# Helicopter_Control_Board2.net
KiCad netlist of a schematic drawn in EAGLE
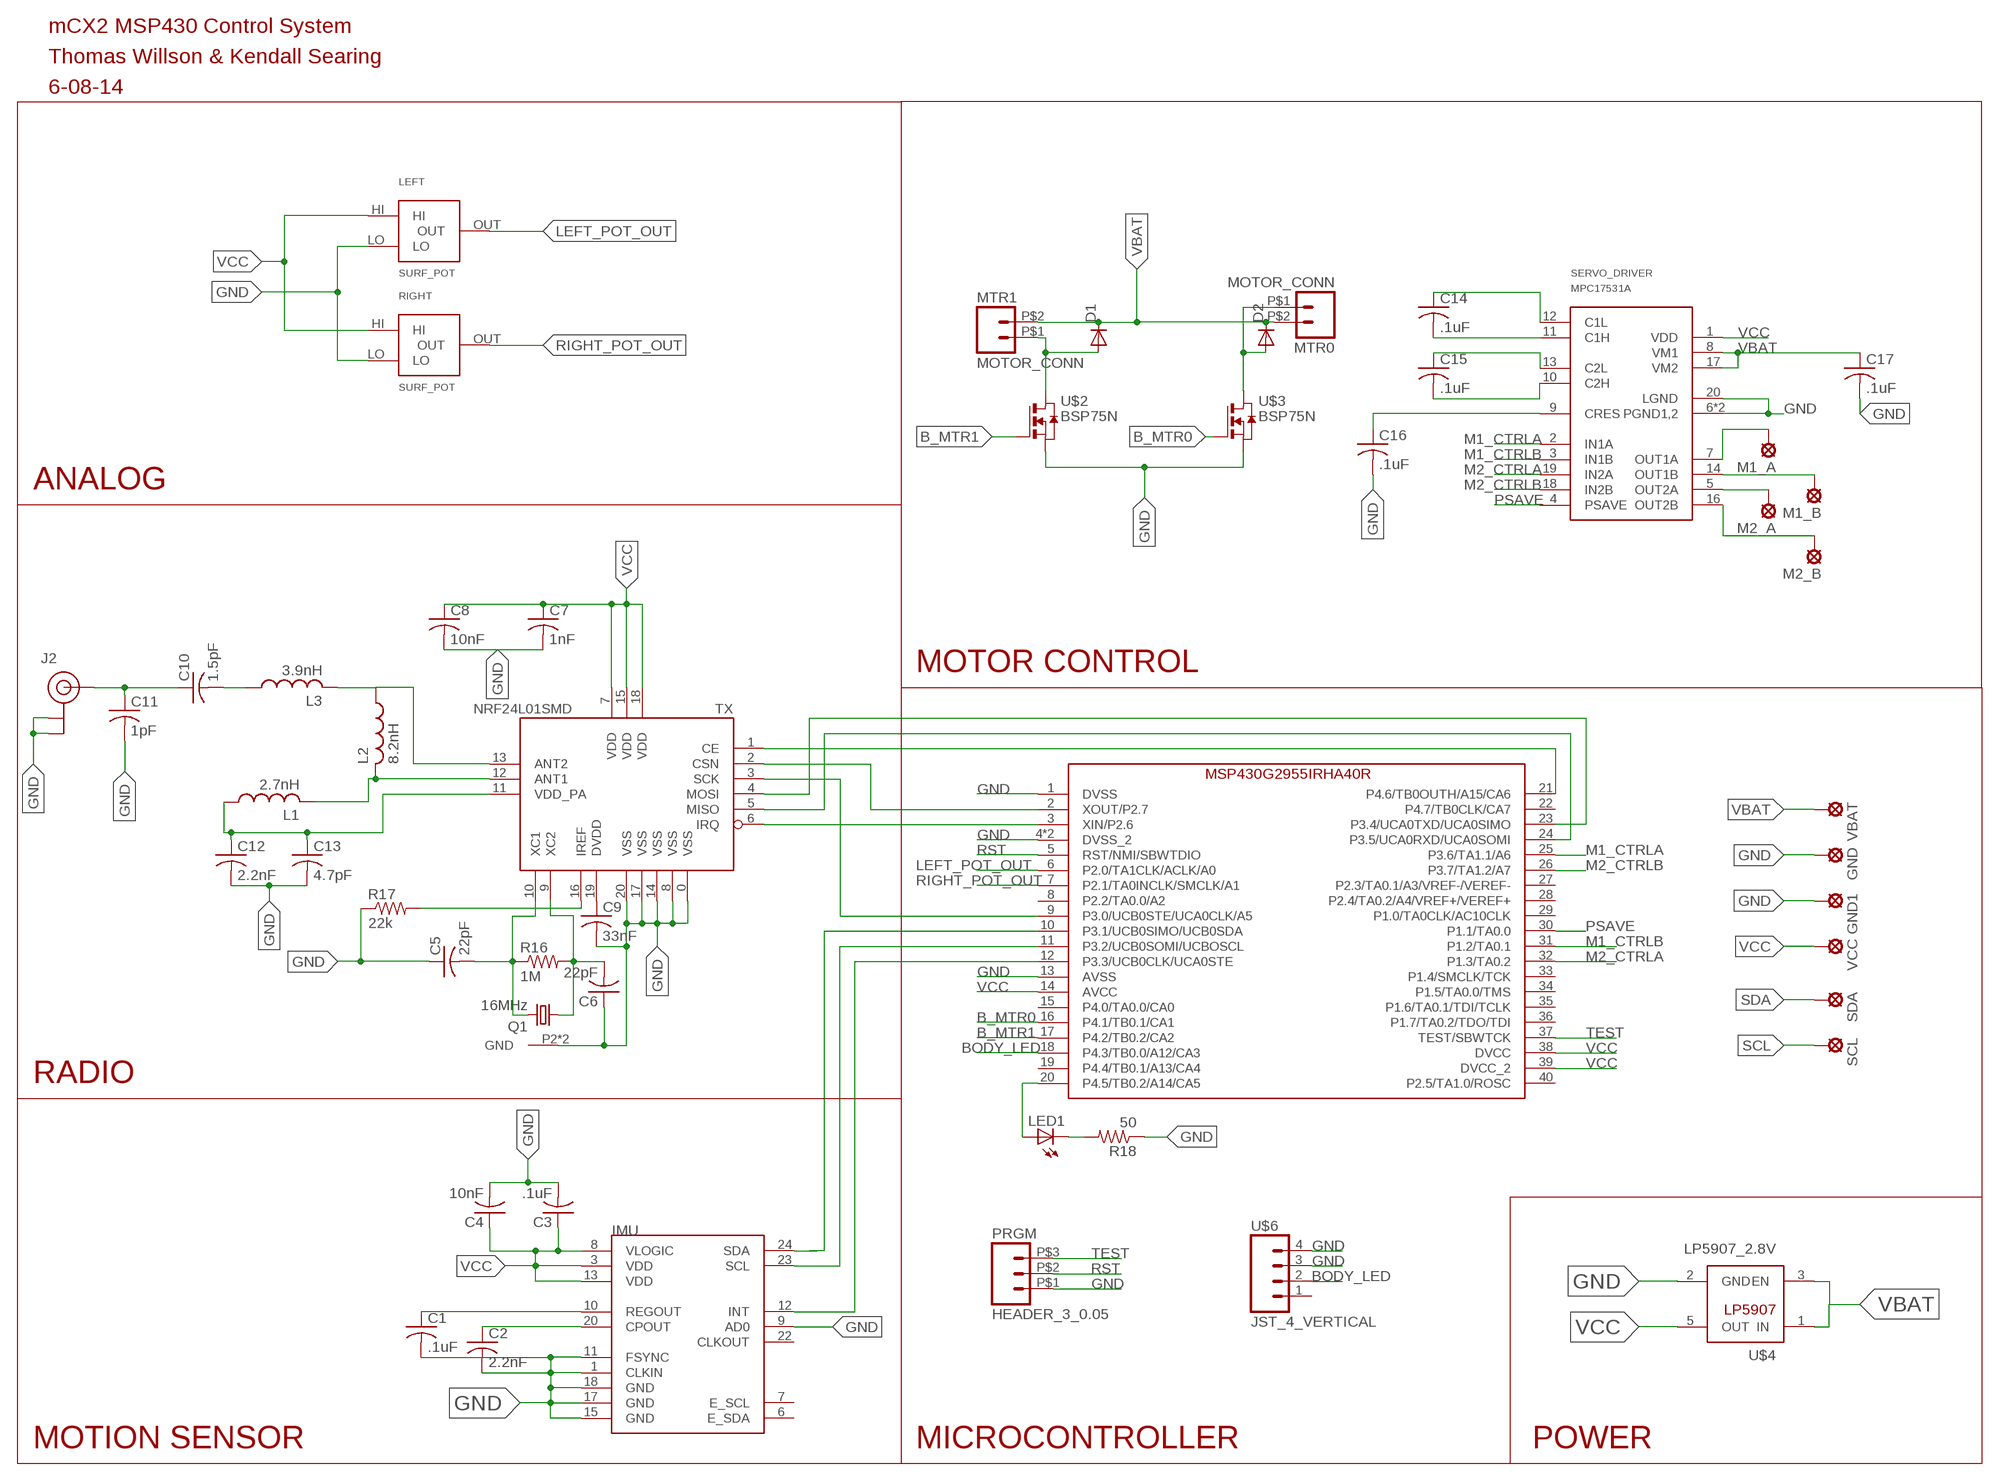
[diagram p0: schematic, sheet 1]

(export (version "E")
  (design (tool "Eeschema 10.0.6"))
  (components
    (comp (ref "C1")
      (value ".1uF")
      (footprint "eagle-import:C0402")
      (libsource (lib "eagle-import") (part "C-USC0402"))
    )
    (comp (ref "C2")
      (value "2.2nF")
      (footprint "eagle-import:C0402")
      (libsource (lib "eagle-import") (part "C-USC0402"))
    )
    (comp (ref "C3")
      (value ".1uF")
      (footprint "eagle-import:C0402")
      (libsource (lib "eagle-import") (part "C-USC0402"))
    )
    (comp (ref "C4")
      (value "10nF")
      (footprint "eagle-import:C0402")
      (libsource (lib "eagle-import") (part "C-USC0402"))
    )
    (comp (ref "C5")
      (value "22pF")
      (footprint "eagle-import:C0402")
      (libsource (lib "eagle-import") (part "C-USC0402"))
    )
    (comp (ref "C6")
      (value "22pF")
      (footprint "eagle-import:C0402")
      (libsource (lib "eagle-import") (part "C-USC0402"))
    )
    (comp (ref "C7")
      (value "1nF")
      (footprint "eagle-import:C0402")
      (libsource (lib "eagle-import") (part "C-USC0402"))
    )
    (comp (ref "C8")
      (value "10nF")
      (footprint "eagle-import:C0402")
      (libsource (lib "eagle-import") (part "C-USC0402"))
    )
    (comp (ref "C9")
      (value "33nF")
      (footprint "eagle-import:C0402")
      (libsource (lib "eagle-import") (part "C-USC0402"))
    )
    (comp (ref "C10")
      (value "1.5pF")
      (footprint "eagle-import:C0402")
      (libsource (lib "eagle-import") (part "C-USC0402"))
    )
    (comp (ref "C11")
      (value "1pF")
      (footprint "eagle-import:C0402")
      (libsource (lib "eagle-import") (part "C-USC0402"))
    )
    (comp (ref "C12")
      (value "2.2nF")
      (footprint "eagle-import:C0402")
      (libsource (lib "eagle-import") (part "C-USC0402"))
    )
    (comp (ref "C13")
      (value "4.7pF")
      (footprint "eagle-import:C0402")
      (libsource (lib "eagle-import") (part "C-USC0402"))
    )
    (comp (ref "C14")
      (value ".1uF")
      (footprint "eagle-import:C0402")
      (libsource (lib "eagle-import") (part "C-USC0402"))
    )
    (comp (ref "C15")
      (value ".1uF")
      (footprint "eagle-import:C0402")
      (libsource (lib "eagle-import") (part "C-USC0402"))
    )
    (comp (ref "C16")
      (value ".1uF")
      (footprint "eagle-import:C0402")
      (libsource (lib "eagle-import") (part "C-USC0402"))
    )
    (comp (ref "C17")
      (value ".1uF")
      (footprint "eagle-import:C0402")
      (libsource (lib "eagle-import") (part "C-USC0402"))
    )
    (comp (ref "D1")
      (value "DIODESMA")
      (footprint "eagle-import:SMA-DIODE")
      (libsource (lib "eagle-import") (part "DIODESMA"))
    )
    (comp (ref "D2")
      (value "DIODESMA")
      (footprint "eagle-import:SMA-DIODE")
      (libsource (lib "eagle-import") (part "DIODESMA"))
    )
    (comp (ref "GND")
      (value "LSP10")
      (footprint "eagle-import:LSP10")
      (libsource (lib "eagle-import") (part "LSP10"))
    )
    (comp (ref "GND1")
      (value "LSP10")
      (footprint "eagle-import:LSP10")
      (libsource (lib "eagle-import") (part "LSP10"))
    )
    (comp (ref "IMU")
      (value "MPU-9150QFN-24-NP")
      (footprint "eagle-import:QFN-24-NP")
      (libsource (lib "eagle-import") (part "MPU-9150QFN-24-NP"))
    )
    (comp (ref "J2")
      (value "U.FL")
      (footprint "eagle-import:U.FL")
      (libsource (lib "eagle-import") (part "U.FL"))
    )
    (comp (ref "L1")
      (value "2.7nH")
      (footprint "eagle-import:R0402")
      (libsource (lib "eagle-import") (part "L-US"))
    )
    (comp (ref "L2")
      (value "8.2nH")
      (footprint "eagle-import:R0402")
      (libsource (lib "eagle-import") (part "L-US"))
    )
    (comp (ref "L3")
      (value "3.9nH")
      (footprint "eagle-import:R0402")
      (libsource (lib "eagle-import") (part "L-US"))
    )
    (comp (ref "LED1")
      (value "LED-BLUE0603")
      (footprint "eagle-import:LED-0603")
      (libsource (lib "eagle-import") (part "LED-BLUE0603"))
    )
    (comp (ref "LEFT")
      (value "SURF_POT")
      (footprint "eagle-import:SURF_POT")
      (libsource (lib "eagle-import") (part "SURF_POT"))
    )
    (comp (ref "M1_A")
      (value "LSP10")
      (footprint "eagle-import:LSP10")
      (libsource (lib "eagle-import") (part "LSP10"))
    )
    (comp (ref "M1_B")
      (value "LSP10")
      (footprint "eagle-import:LSP10")
      (libsource (lib "eagle-import") (part "LSP10"))
    )
    (comp (ref "M2_A")
      (value "LSP10")
      (footprint "eagle-import:LSP10")
      (libsource (lib "eagle-import") (part "LSP10"))
    )
    (comp (ref "M2_B")
      (value "LSP10")
      (footprint "eagle-import:LSP10")
      (libsource (lib "eagle-import") (part "LSP10"))
    )
    (comp (ref "MTR0")
      (value "MOTOR_CONN")
      (footprint "eagle-import:MOTOR_CONN")
      (libsource (lib "eagle-import") (part "MOTOR_CONN"))
    )
    (comp (ref "MTR1")
      (value "MOTOR_CONN")
      (footprint "eagle-import:MOTOR_CONN")
      (libsource (lib "eagle-import") (part "MOTOR_CONN"))
    )
    (comp (ref "PRGM")
      (value "HEADER_3_0.05")
      (footprint "eagle-import:HEADER_3_.05")
      (libsource (lib "eagle-import") (part "HEADER_3_0.05"))
    )
    (comp (ref "Q1")
      (value "16MHz")
      (footprint "eagle-import:TXC-4SMD")
      (libsource (lib "eagle-import") (part "CRYSTAL_16MHZ_12PF_SMD"))
    )
    (comp (ref "R16")
      (value "1M")
      (footprint "eagle-import:R0402")
      (libsource (lib "eagle-import") (part "R-US_R0402"))
    )
    (comp (ref "R17")
      (value "22k")
      (footprint "eagle-import:R0402")
      (libsource (lib "eagle-import") (part "R-US_R0402"))
    )
    (comp (ref "R18")
      (value "50")
      (footprint "eagle-import:R0603")
      (libsource (lib "eagle-import") (part "R-US_R0603"))
    )
    (comp (ref "RIGHT")
      (value "SURF_POT")
      (footprint "eagle-import:SURF_POT")
      (libsource (lib "eagle-import") (part "SURF_POT"))
    )
    (comp (ref "SCL")
      (value "LSP10")
      (footprint "eagle-import:LSP10")
      (libsource (lib "eagle-import") (part "LSP10"))
    )
    (comp (ref "SDA")
      (value "LSP10")
      (footprint "eagle-import:LSP10")
      (libsource (lib "eagle-import") (part "LSP10"))
    )
    (comp (ref "SERVO_DRIVER")
      (value "MPC17531A")
      (footprint "eagle-import:SSOP_20")
      (libsource (lib "eagle-import") (part "MPC17531A"))
    )
    (comp (ref "TX")
      (value "NRF24L01SMD")
      (footprint "eagle-import:QFN20")
      (libsource (lib "eagle-import") (part "NRF24L01SMD"))
    )
    (comp (ref "U$2")
      (value "BSP75N")
      (footprint "eagle-import:PG-SOT-223")
      (libsource (lib "eagle-import") (part "BSP75N"))
    )
    (comp (ref "U$3")
      (value "BSP75N")
      (footprint "eagle-import:PG-SOT-223")
      (libsource (lib "eagle-import") (part "BSP75N"))
    )
    (comp (ref "U$4")
      (value "LP5907_2.8V")
      (footprint "eagle-import:SOT23-DBV")
      (libsource (lib "eagle-import") (part "LP5907"))
    )
    (comp (ref "U$6")
      (value "JST_4_VERTICAL")
      (footprint "eagle-import:JST-4-SMD-VERT-1.0MM")
      (libsource (lib "eagle-import") (part "JST_4_VERTICAL"))
    )
    (comp (ref "U$8")
      (value "G2955IRHA40R")
      (footprint "eagle-import:RHA40")
      (libsource (lib "eagle-import") (part "G2955IRHA40R"))
    )
    (comp (ref "VBAT")
      (value "LSP10")
      (footprint "eagle-import:LSP10")
      (libsource (lib "eagle-import") (part "LSP10"))
    )
    (comp (ref "VCC")
      (value "LSP10")
      (footprint "eagle-import:LSP10")
      (libsource (lib "eagle-import") (part "LSP10"))
    )
  )
  (nets
    (net (code "1") (name "/BODY_LED") (class "Default")
      (node (ref "U$6") (pin "2") (pinfunction "2_2") (pintype "passive"))
      (node (ref "U$8") (pin "18") (pinfunction "P4.3/TB0.0/A12/CA3_18") (pintype "bidirectional"))
    )
    (net (code "2") (name "/M1_CTRLA") (class "Default")
      (node (ref "SERVO_DRIVER") (pin "2") (pinfunction "IN1A_2") (pintype "bidirectional"))
      (node (ref "U$8") (pin "25") (pinfunction "P3.6/TA1.1/A6_25") (pintype "bidirectional"))
    )
    (net (code "3") (name "/M1_CTRLB") (class "Default")
      (node (ref "SERVO_DRIVER") (pin "3") (pinfunction "IN1B_3") (pintype "bidirectional"))
      (node (ref "U$8") (pin "31") (pinfunction "P1.2/TA0.1_31") (pintype "bidirectional"))
    )
    (net (code "4") (name "/M2_CTRLA") (class "Default")
      (node (ref "SERVO_DRIVER") (pin "19") (pinfunction "IN2A_19") (pintype "bidirectional"))
      (node (ref "U$8") (pin "32") (pinfunction "P1.3/TA0.2_32") (pintype "bidirectional"))
    )
    (net (code "5") (name "/M2_CTRLB") (class "Default")
      (node (ref "SERVO_DRIVER") (pin "18") (pinfunction "IN2B_18") (pintype "bidirectional"))
      (node (ref "U$8") (pin "26") (pinfunction "P3.7/TA1.2/A7_26") (pintype "bidirectional"))
    )
    (net (code "6") (name "/PSAVE") (class "Default")
      (node (ref "SERVO_DRIVER") (pin "4") (pinfunction "PSAVE_4") (pintype "bidirectional"))
      (node (ref "U$8") (pin "30") (pinfunction "P1.1/TA0.0_30") (pintype "bidirectional"))
    )
    (net (code "7") (name "/RST") (class "Default")
      (node (ref "PRGM") (pin "P$2") (pinfunction "2_P$2") (pintype "passive"))
      (node (ref "U$8") (pin "5") (pinfunction "RST/NMI/SBWTDIO_5") (pintype "bidirectional"))
    )
    (net (code "8") (name "/TEST") (class "Default")
      (node (ref "PRGM") (pin "P$3") (pinfunction "3_P$3") (pintype "passive"))
      (node (ref "U$8") (pin "37") (pinfunction "TEST/SBWTCK_37") (pintype "bidirectional"))
    )
    (net (code "9") (name "B_MTR0") (class "Default")
      (node (ref "U$3") (pin "1") (pinfunction "G_1") (pintype "passive"))
      (node (ref "U$8") (pin "16") (pinfunction "P4.1/TB0.1/CA1_16") (pintype "bidirectional"))
    )
    (net (code "10") (name "B_MTR1") (class "Default")
      (node (ref "U$2") (pin "1") (pinfunction "G_1") (pintype "passive"))
      (node (ref "U$8") (pin "17") (pinfunction "P4.2/TB0.2/CA2_17") (pintype "bidirectional"))
    )
    (net (code "11") (name "GND") (class "Default")
      (node (ref "C1") (pin "2") (pinfunction "2_2") (pintype "passive"))
      (node (ref "C11") (pin "2") (pinfunction "2_2") (pintype "passive"))
      (node (ref "C12") (pin "2") (pinfunction "2_2") (pintype "passive"))
      (node (ref "C13") (pin "2") (pinfunction "2_2") (pintype "passive"))
      (node (ref "C16") (pin "2") (pinfunction "2_2") (pintype "passive"))
      (node (ref "C17") (pin "2") (pinfunction "2_2") (pintype "passive"))
      (node (ref "C2") (pin "2") (pinfunction "2_2") (pintype "passive"))
      (node (ref "C3") (pin "2") (pinfunction "2_2") (pintype "passive"))
      (node (ref "C4") (pin "2") (pinfunction "2_2") (pintype "passive"))
      (node (ref "C5") (pin "1") (pinfunction "1_1") (pintype "passive"))
      (node (ref "C6") (pin "1") (pinfunction "1_1") (pintype "passive"))
      (node (ref "C7") (pin "2") (pinfunction "2_2") (pintype "passive"))
      (node (ref "C8") (pin "2") (pinfunction "2_2") (pintype "passive"))
      (node (ref "C9") (pin "2") (pinfunction "2_2") (pintype "passive"))
      (node (ref "GND") (pin "MP") (pinfunction "MP_MP") (pintype "passive"))
      (node (ref "GND1") (pin "MP") (pinfunction "MP_MP") (pintype "passive"))
      (node (ref "IMU") (pin "1") (pinfunction "CLKIN_1") (pintype "bidirectional"))
      (node (ref "IMU") (pin "11") (pinfunction "FSYNC_11") (pintype "bidirectional"))
      (node (ref "IMU") (pin "15") (pinfunction "GND_15") (pintype "bidirectional"))
      (node (ref "IMU") (pin "17") (pinfunction "GND_17") (pintype "bidirectional"))
      (node (ref "IMU") (pin "18") (pinfunction "GND_18") (pintype "bidirectional"))
      (node (ref "IMU") (pin "9") (pinfunction "AD0_9") (pintype "bidirectional"))
      (node (ref "J2") (pin "P$1") (pinfunction "GND_P$1") (pintype "bidirectional"))
      (node (ref "J2") (pin "P$2") (pinfunction "GND_P$2") (pintype "bidirectional"))
      (node (ref "LEFT") (pin "LO") (pinfunction "LO_LO") (pintype "bidirectional"))
      (node (ref "PRGM") (pin "P$1") (pinfunction "1_P$1") (pintype "passive"))
      (node (ref "Q1") (pin "P2") (pinfunction "GND_P2") (pintype "bidirectional"))
      (node (ref "Q1") (pin "P4") (pinfunction "GND_P4") (pintype "bidirectional"))
      (node (ref "R17") (pin "1") (pinfunction "1_1") (pintype "passive"))
      (node (ref "R18") (pin "1") (pinfunction "1_1") (pintype "passive"))
      (node (ref "RIGHT") (pin "LO") (pinfunction "LO_LO") (pintype "bidirectional"))
      (node (ref "SERVO_DRIVER") (pin "15") (pinfunction "PGND1,2_15") (pintype "bidirectional"))
      (node (ref "SERVO_DRIVER") (pin "20") (pinfunction "LGND_20") (pintype "bidirectional"))
      (node (ref "SERVO_DRIVER") (pin "6") (pinfunction "PGND1,2_6") (pintype "bidirectional"))
      (node (ref "TX") (pin "0") (pinfunction "VSS_0") (pintype "power_in"))
      (node (ref "TX") (pin "14") (pinfunction "VSS_14") (pintype "power_in"))
      (node (ref "TX") (pin "17") (pinfunction "VSS_17") (pintype "power_in"))
      (node (ref "TX") (pin "20") (pinfunction "VSS_20") (pintype "power_in"))
      (node (ref "TX") (pin "8") (pinfunction "VSS_8") (pintype "power_in"))
      (node (ref "U$2") (pin "3") (pinfunction "S_3") (pintype "passive"))
      (node (ref "U$2") (pin "4") (pinfunction "S_4") (pintype "passive"))
      (node (ref "U$3") (pin "3") (pinfunction "S_3") (pintype "passive"))
      (node (ref "U$3") (pin "4") (pinfunction "S_4") (pintype "passive"))
      (node (ref "U$4") (pin "2") (pinfunction "GND_2") (pintype "bidirectional"))
      (node (ref "U$6") (pin "3") (pinfunction "3_3") (pintype "passive"))
      (node (ref "U$6") (pin "4") (pinfunction "4_4") (pintype "passive"))
      (node (ref "U$8") (pin "1") (pinfunction "DVSS_1") (pintype "bidirectional"))
      (node (ref "U$8") (pin "13") (pinfunction "AVSS_13") (pintype "bidirectional"))
      (node (ref "U$8") (pin "4") (pinfunction "DVSS_2_4") (pintype "bidirectional"))
      (node (ref "U$8") (pin "TP") (pinfunction "DVSS_2_TP") (pintype "bidirectional"))
    )
    (net (code "12") (name "LEFT_POT_OUT") (class "Default")
      (node (ref "LEFT") (pin "OUT") (pinfunction "OUT_OUT") (pintype "bidirectional"))
      (node (ref "U$8") (pin "6") (pinfunction "P2.0/TA1CLK/ACLK/A0_6") (pintype "bidirectional"))
    )
    (net (code "13") (name "Net-(C10-Pad2)") (class "Default")
      (node (ref "C10") (pin "2") (pinfunction "2_2") (pintype "passive"))
      (node (ref "L3") (pin "1") (pinfunction "1_1") (pintype "passive"))
    )
    (net (code "14") (name "Net-(IMU-CPOUT)") (class "Default")
      (node (ref "C2") (pin "1") (pinfunction "1_1") (pintype "passive"))
      (node (ref "IMU") (pin "20") (pinfunction "CPOUT_20") (pintype "bidirectional"))
    )
    (net (code "15") (name "Net-(IMU-INT)") (class "Default")
      (node (ref "IMU") (pin "12") (pinfunction "INT_12") (pintype "bidirectional"))
      (node (ref "U$8") (pin "12") (pinfunction "P3.3/UCB0CLK/UCA0STE_12") (pintype "bidirectional"))
    )
    (net (code "16") (name "Net-(IMU-REGOUT)") (class "Default")
      (node (ref "C1") (pin "1") (pinfunction "1_1") (pintype "passive"))
      (node (ref "IMU") (pin "10") (pinfunction "REGOUT_10") (pintype "bidirectional"))
    )
    (net (code "17") (name "Net-(J2-SIGNAL)") (class "Default")
      (node (ref "C10") (pin "1") (pinfunction "1_1") (pintype "passive"))
      (node (ref "C11") (pin "1") (pinfunction "1_1") (pintype "passive"))
      (node (ref "J2") (pin "P$3") (pinfunction "SIGNAL_P$3") (pintype "bidirectional"))
    )
    (net (code "18") (name "Net-(LED1-PadC)") (class "Default")
      (node (ref "LED1") (pin "C") (pinfunction "C_C") (pintype "passive"))
      (node (ref "R18") (pin "2") (pinfunction "2_2") (pintype "passive"))
    )
    (net (code "19") (name "Net-(MTR0-1)") (class "Default")
      (node (ref "D2") (pin "A") (pinfunction "A_A") (pintype "passive"))
      (node (ref "MTR0") (pin "P$1") (pinfunction "1_P$1") (pintype "passive"))
      (node (ref "U$3") (pin "2") (pinfunction "D_2") (pintype "passive"))
    )
    (net (code "20") (name "Net-(MTR1-1)") (class "Default")
      (node (ref "D1") (pin "A") (pinfunction "A_A") (pintype "passive"))
      (node (ref "MTR1") (pin "P$1") (pinfunction "1_P$1") (pintype "passive"))
      (node (ref "U$2") (pin "2") (pinfunction "D_2") (pintype "passive"))
    )
    (net (code "21") (name "Net-(Q1-1)") (class "Default")
      (node (ref "C6") (pin "2") (pinfunction "2_2") (pintype "passive"))
      (node (ref "Q1") (pin "P1") (pinfunction "1_P1") (pintype "passive"))
      (node (ref "R16") (pin "2") (pinfunction "2_2") (pintype "passive"))
      (node (ref "TX") (pin "9") (pinfunction "XC2_9") (pintype "input"))
    )
    (net (code "22") (name "Net-(Q1-2)") (class "Default")
      (node (ref "C5") (pin "2") (pinfunction "2_2") (pintype "passive"))
      (node (ref "Q1") (pin "P3") (pinfunction "2_P3") (pintype "passive"))
      (node (ref "R16") (pin "1") (pinfunction "1_1") (pintype "passive"))
      (node (ref "TX") (pin "10") (pinfunction "XC1_10") (pintype "input"))
    )
    (net (code "23") (name "Net-(SERVO_DRIVER-C1H)") (class "Default")
      (node (ref "C14") (pin "2") (pinfunction "2_2") (pintype "passive"))
      (node (ref "SERVO_DRIVER") (pin "11") (pinfunction "C1H_11") (pintype "bidirectional"))
    )
    (net (code "24") (name "Net-(SERVO_DRIVER-C1L)") (class "Default")
      (node (ref "C14") (pin "1") (pinfunction "1_1") (pintype "passive"))
      (node (ref "SERVO_DRIVER") (pin "12") (pinfunction "C1L_12") (pintype "bidirectional"))
    )
    (net (code "25") (name "Net-(SERVO_DRIVER-C2H)") (class "Default")
      (node (ref "C15") (pin "2") (pinfunction "2_2") (pintype "passive"))
      (node (ref "SERVO_DRIVER") (pin "10") (pinfunction "C2H_10") (pintype "bidirectional"))
    )
    (net (code "26") (name "Net-(SERVO_DRIVER-C2L)") (class "Default")
      (node (ref "C15") (pin "1") (pinfunction "1_1") (pintype "passive"))
      (node (ref "SERVO_DRIVER") (pin "13") (pinfunction "C2L_13") (pintype "bidirectional"))
    )
    (net (code "27") (name "Net-(SERVO_DRIVER-CRES)") (class "Default")
      (node (ref "C16") (pin "1") (pinfunction "1_1") (pintype "passive"))
      (node (ref "SERVO_DRIVER") (pin "9") (pinfunction "CRES_9") (pintype "bidirectional"))
    )
    (net (code "28") (name "Net-(SERVO_DRIVER-OUT1A)") (class "Default")
      (node (ref "M1_A") (pin "MP") (pinfunction "MP_MP") (pintype "passive"))
      (node (ref "SERVO_DRIVER") (pin "7") (pinfunction "OUT1A_7") (pintype "bidirectional"))
    )
    (net (code "29") (name "Net-(SERVO_DRIVER-OUT1B)") (class "Default")
      (node (ref "M1_B") (pin "MP") (pinfunction "MP_MP") (pintype "passive"))
      (node (ref "SERVO_DRIVER") (pin "14") (pinfunction "OUT1B_14") (pintype "bidirectional"))
    )
    (net (code "30") (name "Net-(SERVO_DRIVER-OUT2A)") (class "Default")
      (node (ref "M2_A") (pin "MP") (pinfunction "MP_MP") (pintype "passive"))
      (node (ref "SERVO_DRIVER") (pin "5") (pinfunction "OUT2A_5") (pintype "bidirectional"))
    )
    (net (code "31") (name "Net-(SERVO_DRIVER-OUT2B)") (class "Default")
      (node (ref "M2_B") (pin "MP") (pinfunction "MP_MP") (pintype "passive"))
      (node (ref "SERVO_DRIVER") (pin "16") (pinfunction "OUT2B_16") (pintype "bidirectional"))
    )
    (net (code "32") (name "Net-(TX-ANT1)") (class "Default")
      (node (ref "L1") (pin "2") (pinfunction "2_2") (pintype "passive"))
      (node (ref "L2") (pin "2") (pinfunction "2_2") (pintype "passive"))
      (node (ref "TX") (pin "12") (pinfunction "ANT1_12") (pintype "output"))
    )
    (net (code "33") (name "Net-(TX-ANT2)") (class "Default")
      (node (ref "L2") (pin "1") (pinfunction "1_1") (pintype "passive"))
      (node (ref "L3") (pin "2") (pinfunction "2_2") (pintype "passive"))
      (node (ref "TX") (pin "13") (pinfunction "ANT2_13") (pintype "output"))
    )
    (net (code "34") (name "Net-(TX-CE)") (class "Default")
      (node (ref "TX") (pin "1") (pinfunction "CE_1") (pintype "input"))
      (node (ref "U$8") (pin "21") (pinfunction "P4.6/TB0OUTH/A15/CA6_21") (pintype "bidirectional"))
    )
    (net (code "35") (name "Net-(TX-CSN)") (class "Default")
      (node (ref "TX") (pin "2") (pinfunction "CSN_2") (pintype "input"))
      (node (ref "U$8") (pin "2") (pinfunction "XOUT/P2.7_2") (pintype "bidirectional"))
    )
    (net (code "36") (name "Net-(TX-DVDD)") (class "Default")
      (node (ref "C9") (pin "1") (pinfunction "1_1") (pintype "passive"))
      (node (ref "TX") (pin "19") (pinfunction "DVDD_19") (pintype "power_in"))
    )
    (net (code "37") (name "Net-(TX-IREF)") (class "Default")
      (node (ref "R17") (pin "2") (pinfunction "2_2") (pintype "passive"))
      (node (ref "TX") (pin "16") (pinfunction "IREF_16") (pintype "input"))
    )
    (net (code "38") (name "Net-(TX-IRQ)") (class "Default")
      (node (ref "TX") (pin "6") (pinfunction "IRQ_6") (pintype "output"))
      (node (ref "U$8") (pin "3") (pinfunction "XIN/P2.6_3") (pintype "bidirectional"))
    )
    (net (code "39") (name "Net-(TX-MISO)") (class "Default")
      (node (ref "TX") (pin "5") (pinfunction "MISO_5") (pintype "output"))
      (node (ref "U$8") (pin "24") (pinfunction "P3.5/UCA0RXD/UCA0SOMI_24") (pintype "bidirectional"))
    )
    (net (code "40") (name "Net-(TX-MOSI)") (class "Default")
      (node (ref "TX") (pin "4") (pinfunction "MOSI_4") (pintype "input"))
      (node (ref "U$8") (pin "23") (pinfunction "P3.4/UCA0TXD/UCA0SIMO_23") (pintype "bidirectional"))
    )
    (net (code "41") (name "Net-(TX-SCK)") (class "Default")
      (node (ref "TX") (pin "3") (pinfunction "SCK_3") (pintype "input"))
      (node (ref "U$8") (pin "9") (pinfunction "P3.0/UCB0STE/UCA0CLK/A5_9") (pintype "bidirectional"))
    )
    (net (code "42") (name "Net-(TX-VDD_PA)") (class "Default")
      (node (ref "C12") (pin "1") (pinfunction "1_1") (pintype "passive"))
      (node (ref "C13") (pin "1") (pinfunction "1_1") (pintype "passive"))
      (node (ref "L1") (pin "1") (pinfunction "1_1") (pintype "passive"))
      (node (ref "TX") (pin "11") (pinfunction "VDD_PA_11") (pintype "power_in"))
    )
    (net (code "43") (name "Net-(U$8-P4.5{slash}TB0.2{slash}A14{slash}CA5)") (class "Default")
      (node (ref "LED1") (pin "A") (pinfunction "A_A") (pintype "passive"))
      (node (ref "U$8") (pin "20") (pinfunction "P4.5/TB0.2/A14/CA5_20") (pintype "bidirectional"))
    )
    (net (code "44") (name "RIGHT_POT_OUT") (class "Default")
      (node (ref "RIGHT") (pin "OUT") (pinfunction "OUT_OUT") (pintype "bidirectional"))
      (node (ref "U$8") (pin "7") (pinfunction "P2.1/TA0INCLK/SMCLK/A1_7") (pintype "bidirectional"))
    )
    (net (code "45") (name "SCL") (class "Default")
      (node (ref "IMU") (pin "23") (pinfunction "SCL_23") (pintype "bidirectional"))
      (node (ref "SCL") (pin "MP") (pinfunction "MP_MP") (pintype "passive"))
      (node (ref "U$8") (pin "11") (pinfunction "P3.2/UCB0SOMI/UCBOSCL_11") (pintype "bidirectional"))
    )
    (net (code "46") (name "SDA") (class "Default")
      (node (ref "IMU") (pin "24") (pinfunction "SDA_24") (pintype "bidirectional"))
      (node (ref "SDA") (pin "MP") (pinfunction "MP_MP") (pintype "passive"))
      (node (ref "U$8") (pin "10") (pinfunction "P3.1/UCB0SIMO/UCB0SDA_10") (pintype "bidirectional"))
    )
    (net (code "47") (name "VBAT") (class "Default")
      (node (ref "C17") (pin "1") (pinfunction "1_1") (pintype "passive"))
      (node (ref "D1") (pin "C") (pinfunction "C_C") (pintype "passive"))
      (node (ref "D2") (pin "C") (pinfunction "C_C") (pintype "passive"))
      (node (ref "MTR0") (pin "P$2") (pinfunction "2_P$2") (pintype "passive"))
      (node (ref "MTR1") (pin "P$2") (pinfunction "2_P$2") (pintype "passive"))
      (node (ref "SERVO_DRIVER") (pin "17") (pinfunction "VM2_17") (pintype "bidirectional"))
      (node (ref "SERVO_DRIVER") (pin "8") (pinfunction "VM1_8") (pintype "bidirectional"))
      (node (ref "U$4") (pin "1") (pinfunction "IN_1") (pintype "bidirectional"))
      (node (ref "U$4") (pin "3") (pinfunction "EN_3") (pintype "bidirectional"))
      (node (ref "VBAT") (pin "MP") (pinfunction "MP_MP") (pintype "passive"))
    )
    (net (code "48") (name "VCC") (class "Default")
      (node (ref "C3") (pin "1") (pinfunction "1_1") (pintype "passive"))
      (node (ref "C4") (pin "1") (pinfunction "1_1") (pintype "passive"))
      (node (ref "C7") (pin "1") (pinfunction "1_1") (pintype "passive"))
      (node (ref "C8") (pin "1") (pinfunction "1_1") (pintype "passive"))
      (node (ref "IMU") (pin "13") (pinfunction "VDD_13") (pintype "bidirectional"))
      (node (ref "IMU") (pin "3") (pinfunction "VDD_3") (pintype "bidirectional"))
      (node (ref "IMU") (pin "8") (pinfunction "VLOGIC_8") (pintype "bidirectional"))
      (node (ref "LEFT") (pin "HI") (pinfunction "HI_HI") (pintype "bidirectional"))
      (node (ref "RIGHT") (pin "HI") (pinfunction "HI_HI") (pintype "bidirectional"))
      (node (ref "SERVO_DRIVER") (pin "1") (pinfunction "VDD_1") (pintype "bidirectional"))
      (node (ref "TX") (pin "15") (pinfunction "VDD_15") (pintype "power_in"))
      (node (ref "TX") (pin "18") (pinfunction "VDD_18") (pintype "power_in"))
      (node (ref "TX") (pin "7") (pinfunction "VDD_7") (pintype "power_in"))
      (node (ref "U$4") (pin "5") (pinfunction "OUT_5") (pintype "bidirectional"))
      (node (ref "U$8") (pin "14") (pinfunction "AVCC_14") (pintype "bidirectional"))
      (node (ref "U$8") (pin "38") (pinfunction "DVCC_38") (pintype "bidirectional"))
      (node (ref "U$8") (pin "39") (pinfunction "DVCC_2_39") (pintype "bidirectional"))
      (node (ref "VCC") (pin "MP") (pinfunction "MP_MP") (pintype "passive"))
    )
    (net (code "49") (name "unconnected-(IMU-CLKOUT-Pad22)") (class "Default")
      (node (ref "IMU") (pin "22") (pinfunction "CLKOUT_22") (pintype "bidirectional"))
    )
    (net (code "50") (name "unconnected-(IMU-E_SCL-Pad7)") (class "Default")
      (node (ref "IMU") (pin "7") (pinfunction "E_SCL_7") (pintype "bidirectional"))
    )
    (net (code "51") (name "unconnected-(IMU-E_SDA-Pad6)") (class "Default")
      (node (ref "IMU") (pin "6") (pinfunction "E_SDA_6") (pintype "bidirectional"))
    )
    (net (code "52") (name "unconnected-(U$6-Pad1)") (class "Default")
      (node (ref "U$6") (pin "1") (pinfunction "1_1") (pintype "passive"))
    )
    (net (code "53") (name "unconnected-(U$8-P1.0{slash}TA0CLK{slash}AC10CLK-Pad29)") (class "Default")
      (node (ref "U$8") (pin "29") (pinfunction "P1.0/TA0CLK/AC10CLK_29") (pintype "bidirectional"))
    )
    (net (code "54") (name "unconnected-(U$8-P1.4{slash}SMCLK{slash}TCK-Pad33)") (class "Default")
      (node (ref "U$8") (pin "33") (pinfunction "P1.4/SMCLK/TCK_33") (pintype "bidirectional"))
    )
    (net (code "55") (name "unconnected-(U$8-P1.5{slash}TA0.0{slash}TMS-Pad34)") (class "Default")
      (node (ref "U$8") (pin "34") (pinfunction "P1.5/TA0.0/TMS_34") (pintype "bidirectional"))
    )
    (net (code "56") (name "unconnected-(U$8-P1.6{slash}TA0.1{slash}TDI{slash}TCLK-Pad35)") (class "Default")
      (node (ref "U$8") (pin "35") (pinfunction "P1.6/TA0.1/TDI/TCLK_35") (pintype "bidirectional"))
    )
    (net (code "57") (name "unconnected-(U$8-P1.7{slash}TA0.2{slash}TDO{slash}TDI-Pad36)") (class "Default")
      (node (ref "U$8") (pin "36") (pinfunction "P1.7/TA0.2/TDO/TDI_36") (pintype "bidirectional"))
    )
    (net (code "58") (name "unconnected-(U$8-P2.2{slash}TA0.0{slash}A2-Pad8)") (class "Default")
      (node (ref "U$8") (pin "8") (pinfunction "P2.2/TA0.0/A2_8") (pintype "bidirectional"))
    )
    (net (code "59") (name "unconnected-(U$8-P2.3{slash}TA0.1{slash}A3{slash}VREF-{slash}VEREF--Pad27)") (class "Default")
      (node (ref "U$8") (pin "27") (pinfunction "P2.3/TA0.1/A3/VREF-/VEREF-_27") (pintype "bidirectional"))
    )
    (net (code "60") (name "unconnected-(U$8-P2.4{slash}TA0.2{slash}A4{slash}VREF+{slash}VEREF+-Pad28)") (class "Default")
      (node (ref "U$8") (pin "28") (pinfunction "P2.4/TA0.2/A4/VREF+/VEREF+_28") (pintype "bidirectional"))
    )
    (net (code "61") (name "unconnected-(U$8-P2.5{slash}TA1.0{slash}ROSC-Pad40)") (class "Default")
      (node (ref "U$8") (pin "40") (pinfunction "P2.5/TA1.0/ROSC_40") (pintype "bidirectional"))
    )
    (net (code "62") (name "unconnected-(U$8-P4.0{slash}TA0.0{slash}CA0-Pad15)") (class "Default")
      (node (ref "U$8") (pin "15") (pinfunction "P4.0/TA0.0/CA0_15") (pintype "bidirectional"))
    )
    (net (code "63") (name "unconnected-(U$8-P4.4{slash}TB0.1{slash}A13{slash}CA4-Pad19)") (class "Default")
      (node (ref "U$8") (pin "19") (pinfunction "P4.4/TB0.1/A13/CA4_19") (pintype "bidirectional"))
    )
    (net (code "64") (name "unconnected-(U$8-P4.7{slash}TB0CLK{slash}CA7-Pad22)") (class "Default")
      (node (ref "U$8") (pin "22") (pinfunction "P4.7/TB0CLK/CA7_22") (pintype "bidirectional"))
    )
  )
)
